# TLS-01.net
KiCad netlist of a schematic drawn in Altium Designer
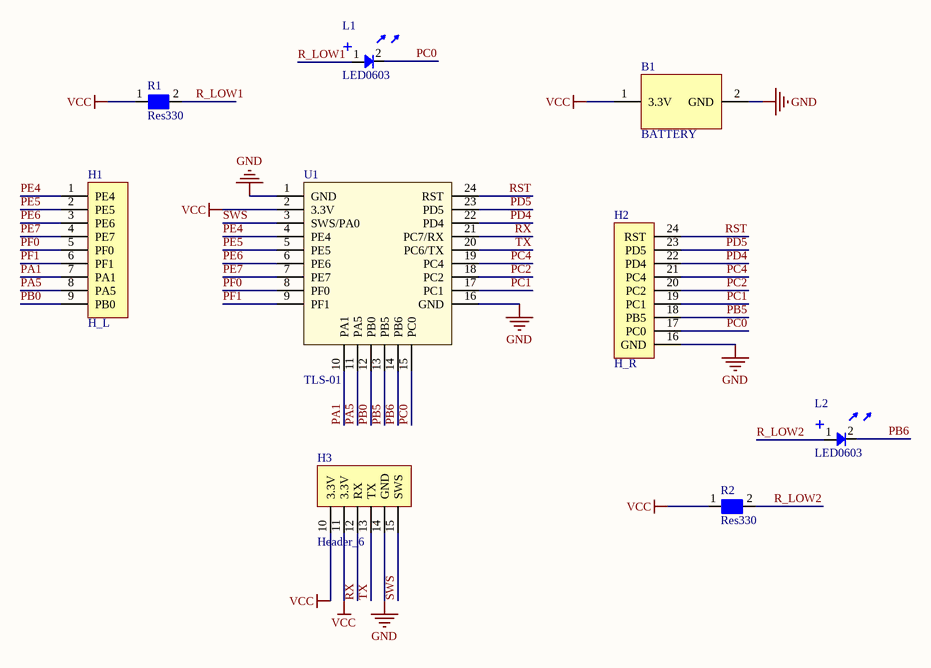
[diagram p0: TLS-01.SchDoc]

(export (version "E")
  (design (tool "Eeschema 10.0.6"))
  (components
    (comp (ref "B1")
      (value "BATTERY")
      (footprint "PCBComponent_1")
      (libsource (lib "Battery") (part "BATTERY"))
    )
    (comp (ref "H1") (value "H_L") (footprint "L") (libsource (lib "Header_L") (part "H_L")))
    (comp (ref "H2") (value "H_R") (footprint "R") (libsource (lib "Header_R") (part "H_R")))
    (comp (ref "H3") (value "Header_6") (footprint "D") (libsource (lib "Header_D") (part "Header_L")))
    (comp (ref "L1") (value "LED0603") (footprint "LED0603") (libsource (lib "LED") (part "LED0603")))
    (comp (ref "L2") (value "LED0603") (footprint "LED0603") (libsource (lib "LED") (part "LED0603")))
    (comp (ref "R1") (value "Res330") (footprint "Res0603") (libsource (lib "Res0603") (part "Res0603")))
    (comp (ref "R2") (value "Res330") (footprint "Res0603") (libsource (lib "Res0603") (part "Res0603")))
    (comp (ref "U1") (value "TLS-01") (footprint "TLS-01") (libsource (lib "JDY-10") (part "TLS-01")))
  )
  (nets
    (net (code "1") (name "/PA1") (class "Default")
      (node (ref "H1") (pin "7") (pinfunction "PA1_7") (pintype "passive"))
      (node (ref "U1") (pin "10") (pinfunction "PA1_10") (pintype "passive"))
    )
    (net (code "2") (name "/PA5") (class "Default")
      (node (ref "H1") (pin "8") (pinfunction "PA5_8") (pintype "passive"))
      (node (ref "U1") (pin "11") (pinfunction "PA5_11") (pintype "passive"))
    )
    (net (code "3") (name "/PB0") (class "Default")
      (node (ref "H1") (pin "9") (pinfunction "PB0_9") (pintype "passive"))
      (node (ref "U1") (pin "12") (pinfunction "PB0_12") (pintype "passive"))
    )
    (net (code "4") (name "/PB5") (class "Default")
      (node (ref "H2") (pin "18") (pinfunction "PB5_18") (pintype "passive"))
      (node (ref "U1") (pin "13") (pinfunction "PB5_13") (pintype "passive"))
    )
    (net (code "5") (name "/PB6") (class "Default")
      (node (ref "L2") (pin "2") (pinfunction "-_2") (pintype "passive"))
      (node (ref "U1") (pin "14") (pinfunction "PB6_14") (pintype "passive"))
    )
    (net (code "6") (name "/PC0") (class "Default")
      (node (ref "H2") (pin "17") (pinfunction "PC0_17") (pintype "passive"))
      (node (ref "L1") (pin "2") (pinfunction "-_2") (pintype "passive"))
      (node (ref "U1") (pin "15") (pinfunction "PC0_15") (pintype "passive"))
    )
    (net (code "7") (name "/PC1") (class "Default")
      (node (ref "H2") (pin "19") (pinfunction "PC1_19") (pintype "passive"))
      (node (ref "U1") (pin "17") (pinfunction "PC1_17") (pintype "passive"))
    )
    (net (code "8") (name "/PC2") (class "Default")
      (node (ref "H2") (pin "20") (pinfunction "PC2_20") (pintype "passive"))
      (node (ref "U1") (pin "18") (pinfunction "PC2_18") (pintype "passive"))
    )
    (net (code "9") (name "/PC4") (class "Default")
      (node (ref "H2") (pin "21") (pinfunction "PC4_21") (pintype "passive"))
      (node (ref "U1") (pin "19") (pinfunction "PC4_19") (pintype "passive"))
    )
    (net (code "10") (name "/PD4") (class "Default")
      (node (ref "H2") (pin "22") (pinfunction "PD4_22") (pintype "passive"))
      (node (ref "U1") (pin "22") (pinfunction "PD4_22") (pintype "passive"))
    )
    (net (code "11") (name "/PD5") (class "Default")
      (node (ref "H2") (pin "23") (pinfunction "PD5_23") (pintype "passive"))
      (node (ref "U1") (pin "23") (pinfunction "PD5_23") (pintype "passive"))
    )
    (net (code "12") (name "/PE4") (class "Default")
      (node (ref "H1") (pin "1") (pinfunction "PE4_1") (pintype "passive"))
      (node (ref "U1") (pin "4") (pinfunction "PE4_4") (pintype "passive"))
    )
    (net (code "13") (name "/PE5") (class "Default")
      (node (ref "H1") (pin "2") (pinfunction "PE5_2") (pintype "passive"))
      (node (ref "U1") (pin "5") (pinfunction "PE5_5") (pintype "passive"))
    )
    (net (code "14") (name "/PE6") (class "Default")
      (node (ref "H1") (pin "3") (pinfunction "PE6_3") (pintype "passive"))
      (node (ref "U1") (pin "6") (pinfunction "PE6_6") (pintype "passive"))
    )
    (net (code "15") (name "/PE7") (class "Default")
      (node (ref "H1") (pin "4") (pinfunction "PE7_4") (pintype "passive"))
      (node (ref "U1") (pin "7") (pinfunction "PE7_7") (pintype "passive"))
    )
    (net (code "16") (name "/PF0") (class "Default")
      (node (ref "H1") (pin "5") (pinfunction "PF0_5") (pintype "passive"))
      (node (ref "U1") (pin "8") (pinfunction "PF0_8") (pintype "passive"))
    )
    (net (code "17") (name "/PF1") (class "Default")
      (node (ref "H1") (pin "6") (pinfunction "PF1_6") (pintype "passive"))
      (node (ref "U1") (pin "9") (pinfunction "PF1_9") (pintype "passive"))
    )
    (net (code "18") (name "/RST") (class "Default")
      (node (ref "H2") (pin "24") (pinfunction "RST_24") (pintype "passive"))
      (node (ref "U1") (pin "24") (pinfunction "RST_24") (pintype "passive"))
    )
    (net (code "19") (name "/RX") (class "Default")
      (node (ref "H3") (pin "12") (pinfunction "RX_12") (pintype "passive"))
      (node (ref "U1") (pin "21") (pinfunction "PC7/RX_21") (pintype "passive"))
    )
    (net (code "20") (name "/R_LOW1") (class "Default")
      (node (ref "L1") (pin "1") (pinfunction "+_1") (pintype "passive"))
      (node (ref "R1") (pin "2") (pintype "passive"))
    )
    (net (code "21") (name "/R_LOW2") (class "Default")
      (node (ref "L2") (pin "1") (pinfunction "+_1") (pintype "passive"))
      (node (ref "R2") (pin "2") (pintype "passive"))
    )
    (net (code "22") (name "/SWS") (class "Default")
      (node (ref "H3") (pin "15") (pinfunction "SWS_15") (pintype "passive"))
      (node (ref "U1") (pin "3") (pinfunction "SWS/PA0_3") (pintype "passive"))
    )
    (net (code "23") (name "/TX") (class "Default")
      (node (ref "H3") (pin "13") (pinfunction "TX_13") (pintype "passive"))
      (node (ref "U1") (pin "20") (pinfunction "PC6/TX_20") (pintype "passive"))
    )
    (net (code "24") (name "GND") (class "Default")
      (node (ref "B1") (pin "2") (pinfunction "GND_2") (pintype "passive"))
      (node (ref "H2") (pin "16") (pinfunction "GND_16") (pintype "passive"))
      (node (ref "H3") (pin "14") (pinfunction "GND_14") (pintype "passive"))
      (node (ref "U1") (pin "1") (pinfunction "GND_1") (pintype "passive"))
      (node (ref "U1") (pin "16") (pinfunction "GND_16") (pintype "passive"))
    )
    (net (code "25") (name "VCC") (class "Default")
      (node (ref "B1") (pin "1") (pinfunction "3.3V_1") (pintype "passive"))
      (node (ref "H3") (pin "10") (pinfunction "3.3V_10") (pintype "passive"))
      (node (ref "H3") (pin "11") (pinfunction "3.3V_11") (pintype "passive"))
      (node (ref "R1") (pin "1") (pintype "passive"))
      (node (ref "R2") (pin "1") (pintype "passive"))
      (node (ref "U1") (pin "2") (pinfunction "3.3V_2") (pintype "passive"))
    )
  )
)
